# Amplifier.net
KiCad netlist of a schematic drawn in Altium Designer
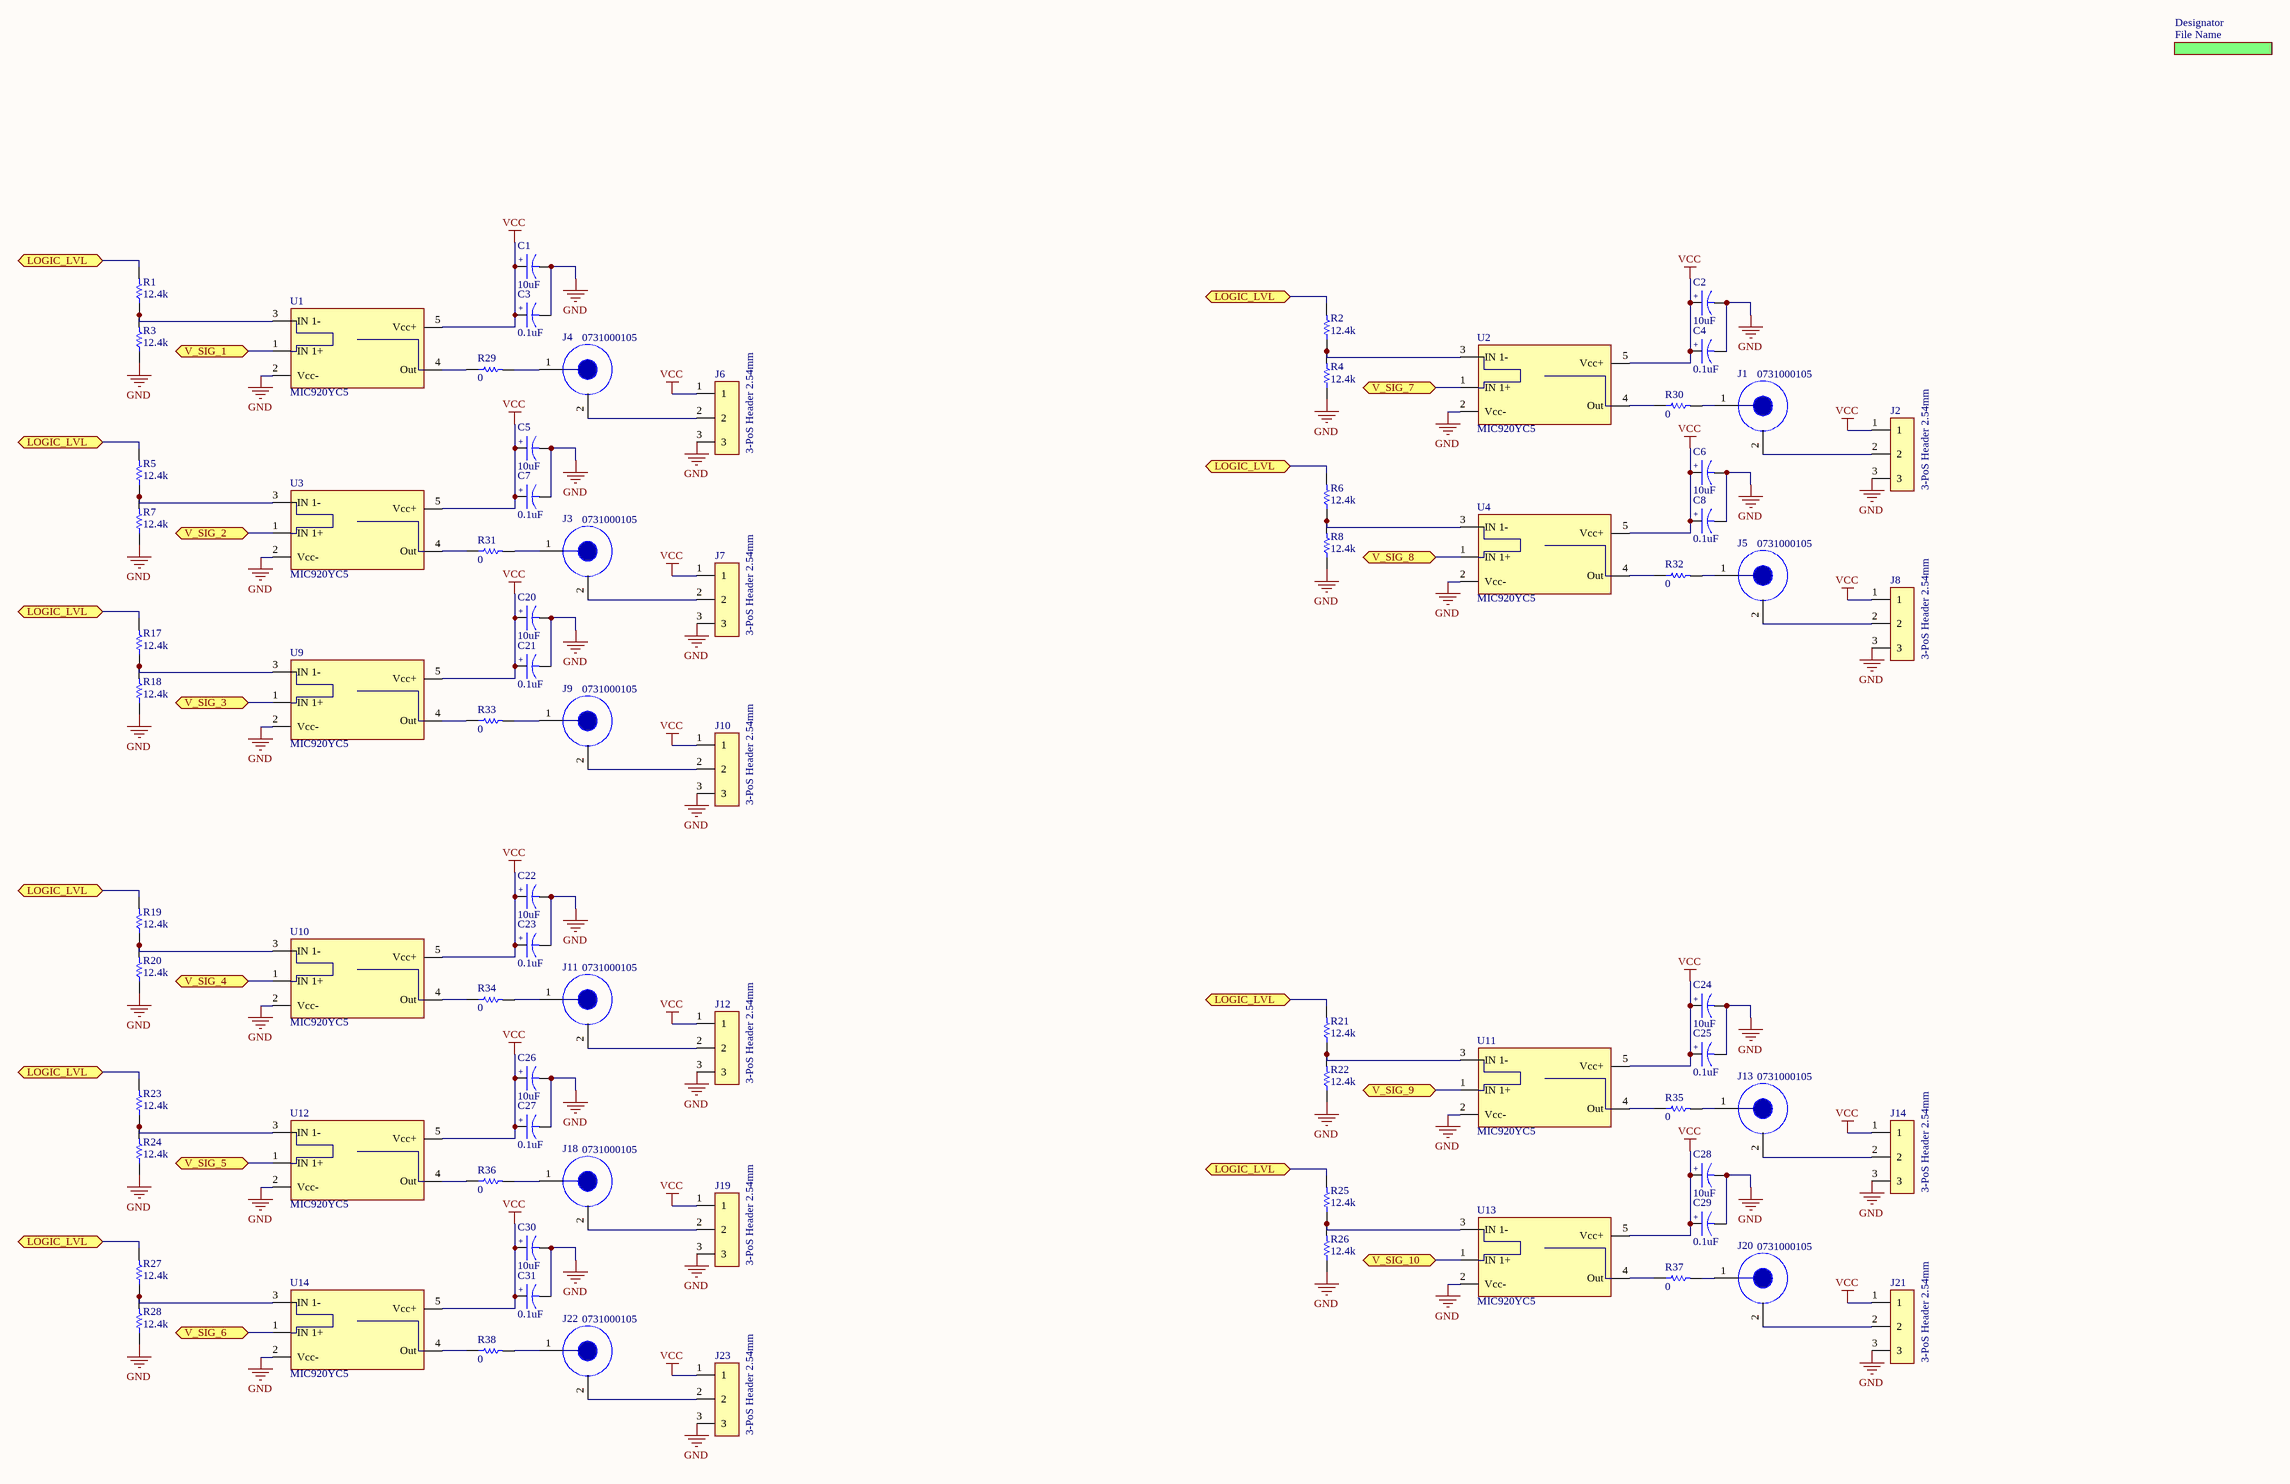
[diagram p0: Amplifier.SchDoc]

(export (version "E")
  (design (tool "Eeschema 10.0.6"))
  (components
    (comp (ref "C1")
      (value "10uF")
      (footprint "0603C")
      (description "Cap Poly")
      (libsource (lib "GENERIC_LIB") (part "CPoly"))
    )
    (comp (ref "C2")
      (value "10uF")
      (footprint "0603C")
      (description "Cap Poly")
      (libsource (lib "GENERIC_LIB") (part "CPoly"))
    )
    (comp (ref "C3")
      (value "0.1uF")
      (footprint "0603C")
      (description "Cap Poly")
      (libsource (lib "GENERIC_LIB") (part "CPoly"))
    )
    (comp (ref "C4")
      (value "0.1uF")
      (footprint "0603C")
      (description "Cap Poly")
      (libsource (lib "GENERIC_LIB") (part "CPoly"))
    )
    (comp (ref "C5")
      (value "10uF")
      (footprint "0603C")
      (description "Cap Poly")
      (libsource (lib "GENERIC_LIB") (part "CPoly"))
    )
    (comp (ref "C6")
      (value "10uF")
      (footprint "0603C")
      (description "Cap Poly")
      (libsource (lib "GENERIC_LIB") (part "CPoly"))
    )
    (comp (ref "C7")
      (value "0.1uF")
      (footprint "0603C")
      (description "Cap Poly")
      (libsource (lib "GENERIC_LIB") (part "CPoly"))
    )
    (comp (ref "C8")
      (value "0.1uF")
      (footprint "0603C")
      (description "Cap Poly")
      (libsource (lib "GENERIC_LIB") (part "CPoly"))
    )
    (comp (ref "C20")
      (value "10uF")
      (footprint "0603C")
      (description "Cap Poly")
      (libsource (lib "GENERIC_LIB") (part "CPoly"))
    )
    (comp (ref "C21")
      (value "0.1uF")
      (footprint "0603C")
      (description "Cap Poly")
      (libsource (lib "GENERIC_LIB") (part "CPoly"))
    )
    (comp (ref "C22")
      (value "10uF")
      (footprint "0603C")
      (description "Cap Poly")
      (libsource (lib "GENERIC_LIB") (part "CPoly"))
    )
    (comp (ref "C23")
      (value "0.1uF")
      (footprint "0603C")
      (description "Cap Poly")
      (libsource (lib "GENERIC_LIB") (part "CPoly"))
    )
    (comp (ref "C24")
      (value "10uF")
      (footprint "0603C")
      (description "Cap Poly")
      (libsource (lib "GENERIC_LIB") (part "CPoly"))
    )
    (comp (ref "C25")
      (value "0.1uF")
      (footprint "0603C")
      (description "Cap Poly")
      (libsource (lib "GENERIC_LIB") (part "CPoly"))
    )
    (comp (ref "C26")
      (value "10uF")
      (footprint "0603C")
      (description "Cap Poly")
      (libsource (lib "GENERIC_LIB") (part "CPoly"))
    )
    (comp (ref "C27")
      (value "0.1uF")
      (footprint "0603C")
      (description "Cap Poly")
      (libsource (lib "GENERIC_LIB") (part "CPoly"))
    )
    (comp (ref "C28")
      (value "10uF")
      (footprint "0603C")
      (description "Cap Poly")
      (libsource (lib "GENERIC_LIB") (part "CPoly"))
    )
    (comp (ref "C29")
      (value "0.1uF")
      (footprint "0603C")
      (description "Cap Poly")
      (libsource (lib "GENERIC_LIB") (part "CPoly"))
    )
    (comp (ref "C30")
      (value "10uF")
      (footprint "0603C")
      (description "Cap Poly")
      (libsource (lib "GENERIC_LIB") (part "CPoly"))
    )
    (comp (ref "C31")
      (value "0.1uF")
      (footprint "0603C")
      (description "Cap Poly")
      (libsource (lib "GENERIC_LIB") (part "CPoly"))
    )
    (comp (ref "J1")
      (value "0731000105")
      (footprint "0731000105")
      (description "BNC Connector Jack, Female Socket 50Ohm Through Hole, Right Angle Solder")
      (libsource (lib "CON_LIB") (part "0731000105"))
    )
    (comp (ref "J2")
      (value "3-PoS Header 2.54mm")
      (footprint "3-POS 2.54mm Pitch Header - duplicate")
      (libsource (lib "CON_LIB") (part "3-PoS Header"))
    )
    (comp (ref "J3")
      (value "0731000105")
      (footprint "0731000105")
      (description "BNC Connector Jack, Female Socket 50Ohm Through Hole, Right Angle Solder")
      (libsource (lib "CON_LIB") (part "0731000105"))
    )
    (comp (ref "J4")
      (value "0731000105")
      (footprint "0731000105")
      (description "BNC Connector Jack, Female Socket 50Ohm Through Hole, Right Angle Solder")
      (libsource (lib "CON_LIB") (part "0731000105"))
    )
    (comp (ref "J5")
      (value "0731000105")
      (footprint "0731000105")
      (description "BNC Connector Jack, Female Socket 50Ohm Through Hole, Right Angle Solder")
      (libsource (lib "CON_LIB") (part "0731000105"))
    )
    (comp (ref "J6")
      (value "3-PoS Header 2.54mm")
      (footprint "3-POS 2.54mm Pitch Header - duplicate")
      (libsource (lib "CON_LIB") (part "3-PoS Header"))
    )
    (comp (ref "J7")
      (value "3-PoS Header 2.54mm")
      (footprint "3-POS 2.54mm Pitch Header - duplicate")
      (libsource (lib "CON_LIB") (part "3-PoS Header"))
    )
    (comp (ref "J8")
      (value "3-PoS Header 2.54mm")
      (footprint "3-POS 2.54mm Pitch Header - duplicate")
      (libsource (lib "CON_LIB") (part "3-PoS Header"))
    )
    (comp (ref "J9")
      (value "0731000105")
      (footprint "0731000105")
      (description "BNC Connector Jack, Female Socket 50Ohm Through Hole, Right Angle Solder")
      (libsource (lib "CON_LIB") (part "0731000105"))
    )
    (comp (ref "J10")
      (value "3-PoS Header 2.54mm")
      (footprint "3-POS 2.54mm Pitch Header - duplicate")
      (libsource (lib "CON_LIB") (part "3-PoS Header"))
    )
    (comp (ref "J11")
      (value "0731000105")
      (footprint "0731000105")
      (description "BNC Connector Jack, Female Socket 50Ohm Through Hole, Right Angle Solder")
      (libsource (lib "CON_LIB") (part "0731000105"))
    )
    (comp (ref "J12")
      (value "3-PoS Header 2.54mm")
      (footprint "3-POS 2.54mm Pitch Header - duplicate")
      (libsource (lib "CON_LIB") (part "3-PoS Header"))
    )
    (comp (ref "J13")
      (value "0731000105")
      (footprint "0731000105")
      (description "BNC Connector Jack, Female Socket 50Ohm Through Hole, Right Angle Solder")
      (libsource (lib "CON_LIB") (part "0731000105"))
    )
    (comp (ref "J14")
      (value "3-PoS Header 2.54mm")
      (footprint "3-POS 2.54mm Pitch Header - duplicate")
      (libsource (lib "CON_LIB") (part "3-PoS Header"))
    )
    (comp (ref "J18")
      (value "0731000105")
      (footprint "0731000105")
      (description "BNC Connector Jack, Female Socket 50Ohm Through Hole, Right Angle Solder")
      (libsource (lib "CON_LIB") (part "0731000105"))
    )
    (comp (ref "J19")
      (value "3-PoS Header 2.54mm")
      (footprint "3-POS 2.54mm Pitch Header - duplicate")
      (libsource (lib "CON_LIB") (part "3-PoS Header"))
    )
    (comp (ref "J20")
      (value "0731000105")
      (footprint "0731000105")
      (description "BNC Connector Jack, Female Socket 50Ohm Through Hole, Right Angle Solder")
      (libsource (lib "CON_LIB") (part "0731000105"))
    )
    (comp (ref "J21")
      (value "3-PoS Header 2.54mm")
      (footprint "3-POS 2.54mm Pitch Header - duplicate")
      (libsource (lib "CON_LIB") (part "3-PoS Header"))
    )
    (comp (ref "J22")
      (value "0731000105")
      (footprint "0731000105")
      (description "BNC Connector Jack, Female Socket 50Ohm Through Hole, Right Angle Solder")
      (libsource (lib "CON_LIB") (part "0731000105"))
    )
    (comp (ref "J23")
      (value "3-PoS Header 2.54mm")
      (footprint "3-POS 2.54mm Pitch Header - duplicate")
      (libsource (lib "CON_LIB") (part "3-PoS Header"))
    )
    (comp (ref "R1")
      (value "12.4k")
      (footprint "0603C")
      (description "Resistor")
      (fields (field (name "TOLERANCE") "5%"))
      (libsource (lib "GENERIC_LIB") (part "R"))
    )
    (comp (ref "R2")
      (value "12.4k")
      (footprint "0603C")
      (description "Resistor")
      (fields (field (name "TOLERANCE") "5%"))
      (libsource (lib "GENERIC_LIB") (part "R"))
    )
    (comp (ref "R3")
      (value "12.4k")
      (footprint "0603C")
      (description "Resistor")
      (fields (field (name "TOLERANCE") "5%"))
      (libsource (lib "GENERIC_LIB") (part "R"))
    )
    (comp (ref "R4")
      (value "12.4k")
      (footprint "0603C")
      (description "Resistor")
      (fields (field (name "TOLERANCE") "5%"))
      (libsource (lib "GENERIC_LIB") (part "R"))
    )
    (comp (ref "R5")
      (value "12.4k")
      (footprint "0603C")
      (description "Resistor")
      (fields (field (name "TOLERANCE") "5%"))
      (libsource (lib "GENERIC_LIB") (part "R"))
    )
    (comp (ref "R6")
      (value "12.4k")
      (footprint "0603C")
      (description "Resistor")
      (fields (field (name "TOLERANCE") "5%"))
      (libsource (lib "GENERIC_LIB") (part "R"))
    )
    (comp (ref "R7")
      (value "12.4k")
      (footprint "0603C")
      (description "Resistor")
      (fields (field (name "TOLERANCE") "5%"))
      (libsource (lib "GENERIC_LIB") (part "R"))
    )
    (comp (ref "R8")
      (value "12.4k")
      (footprint "0603C")
      (description "Resistor")
      (fields (field (name "TOLERANCE") "5%"))
      (libsource (lib "GENERIC_LIB") (part "R"))
    )
    (comp (ref "R17")
      (value "12.4k")
      (footprint "0603C")
      (description "Resistor")
      (fields (field (name "TOLERANCE") "5%"))
      (libsource (lib "GENERIC_LIB") (part "R"))
    )
    (comp (ref "R18")
      (value "12.4k")
      (footprint "0603C")
      (description "Resistor")
      (fields (field (name "TOLERANCE") "5%"))
      (libsource (lib "GENERIC_LIB") (part "R"))
    )
    (comp (ref "R19")
      (value "12.4k")
      (footprint "0603C")
      (description "Resistor")
      (fields (field (name "TOLERANCE") "5%"))
      (libsource (lib "GENERIC_LIB") (part "R"))
    )
    (comp (ref "R20")
      (value "12.4k")
      (footprint "0603C")
      (description "Resistor")
      (fields (field (name "TOLERANCE") "5%"))
      (libsource (lib "GENERIC_LIB") (part "R"))
    )
    (comp (ref "R21")
      (value "12.4k")
      (footprint "0603C")
      (description "Resistor")
      (fields (field (name "TOLERANCE") "5%"))
      (libsource (lib "GENERIC_LIB") (part "R"))
    )
    (comp (ref "R22")
      (value "12.4k")
      (footprint "0603C")
      (description "Resistor")
      (fields (field (name "TOLERANCE") "5%"))
      (libsource (lib "GENERIC_LIB") (part "R"))
    )
    (comp (ref "R23")
      (value "12.4k")
      (footprint "0603C")
      (description "Resistor")
      (fields (field (name "TOLERANCE") "5%"))
      (libsource (lib "GENERIC_LIB") (part "R"))
    )
    (comp (ref "R24")
      (value "12.4k")
      (footprint "0603C")
      (description "Resistor")
      (fields (field (name "TOLERANCE") "5%"))
      (libsource (lib "GENERIC_LIB") (part "R"))
    )
    (comp (ref "R25")
      (value "12.4k")
      (footprint "0603C")
      (description "Resistor")
      (fields (field (name "TOLERANCE") "5%"))
      (libsource (lib "GENERIC_LIB") (part "R"))
    )
    (comp (ref "R26")
      (value "12.4k")
      (footprint "0603C")
      (description "Resistor")
      (fields (field (name "TOLERANCE") "5%"))
      (libsource (lib "GENERIC_LIB") (part "R"))
    )
    (comp (ref "R27")
      (value "12.4k")
      (footprint "0603C")
      (description "Resistor")
      (fields (field (name "TOLERANCE") "5%"))
      (libsource (lib "GENERIC_LIB") (part "R"))
    )
    (comp (ref "R28")
      (value "12.4k")
      (footprint "0603C")
      (description "Resistor")
      (fields (field (name "TOLERANCE") "5%"))
      (libsource (lib "GENERIC_LIB") (part "R"))
    )
    (comp (ref "R29")
      (value "0")
      (footprint "1206C")
      (description "Resistor")
      (fields (field (name "TOLERANCE") "5%"))
      (libsource (lib "GENERIC_LIB") (part "R"))
    )
    (comp (ref "R30")
      (value "0")
      (footprint "1206C")
      (description "Resistor")
      (fields (field (name "TOLERANCE") "5%"))
      (libsource (lib "GENERIC_LIB") (part "R"))
    )
    (comp (ref "R31")
      (value "0")
      (footprint "1206C")
      (description "Resistor")
      (fields (field (name "TOLERANCE") "5%"))
      (libsource (lib "GENERIC_LIB") (part "R"))
    )
    (comp (ref "R32")
      (value "0")
      (footprint "1206C")
      (description "Resistor")
      (fields (field (name "TOLERANCE") "5%"))
      (libsource (lib "GENERIC_LIB") (part "R"))
    )
    (comp (ref "R33")
      (value "0")
      (footprint "1206C")
      (description "Resistor")
      (fields (field (name "TOLERANCE") "5%"))
      (libsource (lib "GENERIC_LIB") (part "R"))
    )
    (comp (ref "R34")
      (value "0")
      (footprint "1206C")
      (description "Resistor")
      (fields (field (name "TOLERANCE") "5%"))
      (libsource (lib "GENERIC_LIB") (part "R"))
    )
    (comp (ref "R35")
      (value "0")
      (footprint "1206C")
      (description "Resistor")
      (fields (field (name "TOLERANCE") "5%"))
      (libsource (lib "GENERIC_LIB") (part "R"))
    )
    (comp (ref "R36")
      (value "0")
      (footprint "1206C")
      (description "Resistor")
      (fields (field (name "TOLERANCE") "5%"))
      (libsource (lib "GENERIC_LIB") (part "R"))
    )
    (comp (ref "R37")
      (value "0")
      (footprint "1206C")
      (description "Resistor")
      (fields (field (name "TOLERANCE") "5%"))
      (libsource (lib "GENERIC_LIB") (part "R"))
    )
    (comp (ref "R38")
      (value "0")
      (footprint "1206C")
      (description "Resistor")
      (fields (field (name "TOLERANCE") "5%"))
      (libsource (lib "GENERIC_LIB") (part "R"))
    )
    (comp (ref "U1")
      (value "MIC920YC5")
      (footprint "MIC920")
      (description "General Purpose Amplifier 1 Circuit SC-70-5")
      (libsource (lib "ANALOG_LIB") (part "MIC920YC5-TR"))
    )
    (comp (ref "U2")
      (value "MIC920YC5")
      (footprint "MIC920")
      (description "General Purpose Amplifier 1 Circuit SC-70-5")
      (libsource (lib "ANALOG_LIB") (part "MIC920YC5-TR"))
    )
    (comp (ref "U3")
      (value "MIC920YC5")
      (footprint "MIC920")
      (description "General Purpose Amplifier 1 Circuit SC-70-5")
      (libsource (lib "ANALOG_LIB") (part "MIC920YC5-TR"))
    )
    (comp (ref "U4")
      (value "MIC920YC5")
      (footprint "MIC920")
      (description "General Purpose Amplifier 1 Circuit SC-70-5")
      (libsource (lib "ANALOG_LIB") (part "MIC920YC5-TR"))
    )
    (comp (ref "U9")
      (value "MIC920YC5")
      (footprint "MIC920")
      (description "General Purpose Amplifier 1 Circuit SC-70-5")
      (libsource (lib "ANALOG_LIB") (part "MIC920YC5-TR"))
    )
    (comp (ref "U10")
      (value "MIC920YC5")
      (footprint "MIC920")
      (description "General Purpose Amplifier 1 Circuit SC-70-5")
      (libsource (lib "ANALOG_LIB") (part "MIC920YC5-TR"))
    )
    (comp (ref "U11")
      (value "MIC920YC5")
      (footprint "MIC920")
      (description "General Purpose Amplifier 1 Circuit SC-70-5")
      (libsource (lib "ANALOG_LIB") (part "MIC920YC5-TR"))
    )
    (comp (ref "U12")
      (value "MIC920YC5")
      (footprint "MIC920")
      (description "General Purpose Amplifier 1 Circuit SC-70-5")
      (libsource (lib "ANALOG_LIB") (part "MIC920YC5-TR"))
    )
    (comp (ref "U13")
      (value "MIC920YC5")
      (footprint "MIC920")
      (description "General Purpose Amplifier 1 Circuit SC-70-5")
      (libsource (lib "ANALOG_LIB") (part "MIC920YC5-TR"))
    )
    (comp (ref "U14")
      (value "MIC920YC5")
      (footprint "MIC920")
      (description "General Purpose Amplifier 1 Circuit SC-70-5")
      (libsource (lib "ANALOG_LIB") (part "MIC920YC5-TR"))
    )
  )
  (nets
    (net (code "1") (name "/LOGIC_LVL") (class "Default")
      (node (ref "R1") (pin "2") (pinfunction "2_2") (pintype "passive"))
      (node (ref "R17") (pin "2") (pinfunction "2_2") (pintype "passive"))
      (node (ref "R19") (pin "2") (pinfunction "2_2") (pintype "passive"))
      (node (ref "R2") (pin "2") (pinfunction "2_2") (pintype "passive"))
      (node (ref "R21") (pin "2") (pinfunction "2_2") (pintype "passive"))
      (node (ref "R23") (pin "2") (pinfunction "2_2") (pintype "passive"))
      (node (ref "R25") (pin "2") (pinfunction "2_2") (pintype "passive"))
      (node (ref "R27") (pin "2") (pinfunction "2_2") (pintype "passive"))
      (node (ref "R5") (pin "2") (pinfunction "2_2") (pintype "passive"))
      (node (ref "R6") (pin "2") (pinfunction "2_2") (pintype "passive"))
    )
    (net (code "2") (name "/V_SIG_1") (class "Default")
      (node (ref "U1") (pin "1") (pinfunction "IN_1+_1") (pintype "passive"))
    )
    (net (code "3") (name "/V_SIG_2") (class "Default")
      (node (ref "U3") (pin "1") (pinfunction "IN_1+_1") (pintype "passive"))
    )
    (net (code "4") (name "/V_SIG_3") (class "Default")
      (node (ref "U9") (pin "1") (pinfunction "IN_1+_1") (pintype "passive"))
    )
    (net (code "5") (name "/V_SIG_4") (class "Default")
      (node (ref "U10") (pin "1") (pinfunction "IN_1+_1") (pintype "passive"))
    )
    (net (code "6") (name "/V_SIG_5") (class "Default")
      (node (ref "U12") (pin "1") (pinfunction "IN_1+_1") (pintype "passive"))
    )
    (net (code "7") (name "/V_SIG_6") (class "Default")
      (node (ref "U14") (pin "1") (pinfunction "IN_1+_1") (pintype "passive"))
    )
    (net (code "8") (name "/V_SIG_7") (class "Default")
      (node (ref "U2") (pin "1") (pinfunction "IN_1+_1") (pintype "passive"))
    )
    (net (code "9") (name "/V_SIG_8") (class "Default")
      (node (ref "U4") (pin "1") (pinfunction "IN_1+_1") (pintype "passive"))
    )
    (net (code "10") (name "/V_SIG_9") (class "Default")
      (node (ref "U11") (pin "1") (pinfunction "IN_1+_1") (pintype "passive"))
    )
    (net (code "11") (name "/V_SIG_10") (class "Default")
      (node (ref "U13") (pin "1") (pinfunction "IN_1+_1") (pintype "passive"))
    )
    (net (code "12") (name "GND") (class "Default")
      (node (ref "C1") (pin "2") (pinfunction "2_2") (pintype "passive"))
      (node (ref "C2") (pin "2") (pinfunction "2_2") (pintype "passive"))
      (node (ref "C20") (pin "2") (pinfunction "2_2") (pintype "passive"))
      (node (ref "C21") (pin "2") (pinfunction "2_2") (pintype "passive"))
      (node (ref "C22") (pin "2") (pinfunction "2_2") (pintype "passive"))
      (node (ref "C23") (pin "2") (pinfunction "2_2") (pintype "passive"))
      (node (ref "C24") (pin "2") (pinfunction "2_2") (pintype "passive"))
      (node (ref "C25") (pin "2") (pinfunction "2_2") (pintype "passive"))
      (node (ref "C26") (pin "2") (pinfunction "2_2") (pintype "passive"))
      (node (ref "C27") (pin "2") (pinfunction "2_2") (pintype "passive"))
      (node (ref "C28") (pin "2") (pinfunction "2_2") (pintype "passive"))
      (node (ref "C29") (pin "2") (pinfunction "2_2") (pintype "passive"))
      (node (ref "C3") (pin "2") (pinfunction "2_2") (pintype "passive"))
      (node (ref "C30") (pin "2") (pinfunction "2_2") (pintype "passive"))
      (node (ref "C31") (pin "2") (pinfunction "2_2") (pintype "passive"))
      (node (ref "C4") (pin "2") (pinfunction "2_2") (pintype "passive"))
      (node (ref "C5") (pin "2") (pinfunction "2_2") (pintype "passive"))
      (node (ref "C6") (pin "2") (pinfunction "2_2") (pintype "passive"))
      (node (ref "C7") (pin "2") (pinfunction "2_2") (pintype "passive"))
      (node (ref "C8") (pin "2") (pinfunction "2_2") (pintype "passive"))
      (node (ref "J10") (pin "3") (pinfunction "3_3") (pintype "passive"))
      (node (ref "J12") (pin "3") (pinfunction "3_3") (pintype "passive"))
      (node (ref "J14") (pin "3") (pinfunction "3_3") (pintype "passive"))
      (node (ref "J19") (pin "3") (pinfunction "3_3") (pintype "passive"))
      (node (ref "J2") (pin "3") (pinfunction "3_3") (pintype "passive"))
      (node (ref "J21") (pin "3") (pinfunction "3_3") (pintype "passive"))
      (node (ref "J23") (pin "3") (pinfunction "3_3") (pintype "passive"))
      (node (ref "J6") (pin "3") (pinfunction "3_3") (pintype "passive"))
      (node (ref "J7") (pin "3") (pinfunction "3_3") (pintype "passive"))
      (node (ref "J8") (pin "3") (pinfunction "3_3") (pintype "passive"))
      (node (ref "R18") (pin "1") (pinfunction "1_1") (pintype "passive"))
      (node (ref "R20") (pin "1") (pinfunction "1_1") (pintype "passive"))
      (node (ref "R22") (pin "1") (pinfunction "1_1") (pintype "passive"))
      (node (ref "R24") (pin "1") (pinfunction "1_1") (pintype "passive"))
      (node (ref "R26") (pin "1") (pinfunction "1_1") (pintype "passive"))
      (node (ref "R28") (pin "1") (pinfunction "1_1") (pintype "passive"))
      (node (ref "R3") (pin "1") (pinfunction "1_1") (pintype "passive"))
      (node (ref "R4") (pin "1") (pinfunction "1_1") (pintype "passive"))
      (node (ref "R7") (pin "1") (pinfunction "1_1") (pintype "passive"))
      (node (ref "R8") (pin "1") (pinfunction "1_1") (pintype "passive"))
      (node (ref "U1") (pin "2") (pinfunction "Vcc-_2") (pintype "passive"))
      (node (ref "U10") (pin "2") (pinfunction "Vcc-_2") (pintype "passive"))
      (node (ref "U11") (pin "2") (pinfunction "Vcc-_2") (pintype "passive"))
      (node (ref "U12") (pin "2") (pinfunction "Vcc-_2") (pintype "passive"))
      (node (ref "U13") (pin "2") (pinfunction "Vcc-_2") (pintype "passive"))
      (node (ref "U14") (pin "2") (pinfunction "Vcc-_2") (pintype "passive"))
      (node (ref "U2") (pin "2") (pinfunction "Vcc-_2") (pintype "passive"))
      (node (ref "U3") (pin "2") (pinfunction "Vcc-_2") (pintype "passive"))
      (node (ref "U4") (pin "2") (pinfunction "Vcc-_2") (pintype "passive"))
      (node (ref "U9") (pin "2") (pinfunction "Vcc-_2") (pintype "passive"))
    )
    (net (code "13") (name "Net-(J1-Pad1)") (class "Default")
      (node (ref "J1") (pin "1") (pinfunction "1_1") (pintype "passive"))
      (node (ref "R30") (pin "2") (pinfunction "2_2") (pintype "passive"))
    )
    (net (code "14") (name "Net-(J1-Pad2)") (class "Default")
      (node (ref "J1") (pin "2") (pinfunction "2_2") (pintype "passive"))
      (node (ref "J2") (pin "2") (pinfunction "2_2") (pintype "passive"))
    )
    (net (code "15") (name "Net-(J3-Pad1)") (class "Default")
      (node (ref "J3") (pin "1") (pinfunction "1_1") (pintype "passive"))
      (node (ref "R31") (pin "2") (pinfunction "2_2") (pintype "passive"))
    )
    (net (code "16") (name "Net-(J3-Pad2)") (class "Default")
      (node (ref "J3") (pin "2") (pinfunction "2_2") (pintype "passive"))
      (node (ref "J7") (pin "2") (pinfunction "2_2") (pintype "passive"))
    )
    (net (code "17") (name "Net-(J4-Pad1)") (class "Default")
      (node (ref "J4") (pin "1") (pinfunction "1_1") (pintype "passive"))
      (node (ref "R29") (pin "2") (pinfunction "2_2") (pintype "passive"))
    )
    (net (code "18") (name "Net-(J4-Pad2)") (class "Default")
      (node (ref "J4") (pin "2") (pinfunction "2_2") (pintype "passive"))
      (node (ref "J6") (pin "2") (pinfunction "2_2") (pintype "passive"))
    )
    (net (code "19") (name "Net-(J5-Pad1)") (class "Default")
      (node (ref "J5") (pin "1") (pinfunction "1_1") (pintype "passive"))
      (node (ref "R32") (pin "2") (pinfunction "2_2") (pintype "passive"))
    )
    (net (code "20") (name "Net-(J5-Pad2)") (class "Default")
      (node (ref "J5") (pin "2") (pinfunction "2_2") (pintype "passive"))
      (node (ref "J8") (pin "2") (pinfunction "2_2") (pintype "passive"))
    )
    (net (code "21") (name "Net-(J9-Pad1)") (class "Default")
      (node (ref "J9") (pin "1") (pinfunction "1_1") (pintype "passive"))
      (node (ref "R33") (pin "2") (pinfunction "2_2") (pintype "passive"))
    )
    (net (code "22") (name "Net-(J10-Pad2)") (class "Default")
      (node (ref "J10") (pin "2") (pinfunction "2_2") (pintype "passive"))
      (node (ref "J9") (pin "2") (pinfunction "2_2") (pintype "passive"))
    )
    (net (code "23") (name "Net-(J11-Pad1)") (class "Default")
      (node (ref "J11") (pin "1") (pinfunction "1_1") (pintype "passive"))
      (node (ref "R34") (pin "2") (pinfunction "2_2") (pintype "passive"))
    )
    (net (code "24") (name "Net-(J11-Pad2)") (class "Default")
      (node (ref "J11") (pin "2") (pinfunction "2_2") (pintype "passive"))
      (node (ref "J12") (pin "2") (pinfunction "2_2") (pintype "passive"))
    )
    (net (code "25") (name "Net-(J13-Pad1)") (class "Default")
      (node (ref "J13") (pin "1") (pinfunction "1_1") (pintype "passive"))
      (node (ref "R35") (pin "2") (pinfunction "2_2") (pintype "passive"))
    )
    (net (code "26") (name "Net-(J13-Pad2)") (class "Default")
      (node (ref "J13") (pin "2") (pinfunction "2_2") (pintype "passive"))
      (node (ref "J14") (pin "2") (pinfunction "2_2") (pintype "passive"))
    )
    (net (code "27") (name "Net-(J18-Pad1)") (class "Default")
      (node (ref "J18") (pin "1") (pinfunction "1_1") (pintype "passive"))
      (node (ref "R36") (pin "2") (pinfunction "2_2") (pintype "passive"))
    )
    (net (code "28") (name "Net-(J18-Pad2)") (class "Default")
      (node (ref "J18") (pin "2") (pinfunction "2_2") (pintype "passive"))
      (node (ref "J19") (pin "2") (pinfunction "2_2") (pintype "passive"))
    )
    (net (code "29") (name "Net-(J20-Pad1)") (class "Default")
      (node (ref "J20") (pin "1") (pinfunction "1_1") (pintype "passive"))
      (node (ref "R37") (pin "2") (pinfunction "2_2") (pintype "passive"))
    )
    (net (code "30") (name "Net-(J20-Pad2)") (class "Default")
      (node (ref "J20") (pin "2") (pinfunction "2_2") (pintype "passive"))
      (node (ref "J21") (pin "2") (pinfunction "2_2") (pintype "passive"))
    )
    (net (code "31") (name "Net-(J22-Pad1)") (class "Default")
      (node (ref "J22") (pin "1") (pinfunction "1_1") (pintype "passive"))
      (node (ref "R38") (pin "2") (pinfunction "2_2") (pintype "passive"))
    )
    (net (code "32") (name "Net-(J22-Pad2)") (class "Default")
      (node (ref "J22") (pin "2") (pinfunction "2_2") (pintype "passive"))
      (node (ref "J23") (pin "2") (pinfunction "2_2") (pintype "passive"))
    )
    (net (code "33") (name "Net-(U1-IN_1-)") (class "Default")
      (node (ref "R1") (pin "1") (pinfunction "1_1") (pintype "passive"))
      (node (ref "R3") (pin "2") (pinfunction "2_2") (pintype "passive"))
      (node (ref "U1") (pin "3") (pinfunction "IN_1-_3") (pintype "passive"))
    )
    (net (code "34") (name "Net-(U1-Out)") (class "Default")
      (node (ref "R29") (pin "1") (pinfunction "1_1") (pintype "passive"))
      (node (ref "U1") (pin "4") (pinfunction "Out_4") (pintype "passive"))
    )
    (net (code "35") (name "Net-(U2-IN_1-)") (class "Default")
      (node (ref "R2") (pin "1") (pinfunction "1_1") (pintype "passive"))
      (node (ref "R4") (pin "2") (pinfunction "2_2") (pintype "passive"))
      (node (ref "U2") (pin "3") (pinfunction "IN_1-_3") (pintype "passive"))
    )
    (net (code "36") (name "Net-(U2-Out)") (class "Default")
      (node (ref "R30") (pin "1") (pinfunction "1_1") (pintype "passive"))
      (node (ref "U2") (pin "4") (pinfunction "Out_4") (pintype "passive"))
    )
    (net (code "37") (name "Net-(U3-IN_1-)") (class "Default")
      (node (ref "R5") (pin "1") (pinfunction "1_1") (pintype "passive"))
      (node (ref "R7") (pin "2") (pinfunction "2_2") (pintype "passive"))
      (node (ref "U3") (pin "3") (pinfunction "IN_1-_3") (pintype "passive"))
    )
    (net (code "38") (name "Net-(U3-Out)") (class "Default")
      (node (ref "R31") (pin "1") (pinfunction "1_1") (pintype "passive"))
      (node (ref "U3") (pin "4") (pinfunction "Out_4") (pintype "passive"))
    )
    (net (code "39") (name "Net-(U4-IN_1-)") (class "Default")
      (node (ref "R6") (pin "1") (pinfunction "1_1") (pintype "passive"))
      (node (ref "R8") (pin "2") (pinfunction "2_2") (pintype "passive"))
      (node (ref "U4") (pin "3") (pinfunction "IN_1-_3") (pintype "passive"))
    )
    (net (code "40") (name "Net-(U4-Out)") (class "Default")
      (node (ref "R32") (pin "1") (pinfunction "1_1") (pintype "passive"))
      (node (ref "U4") (pin "4") (pinfunction "Out_4") (pintype "passive"))
    )
    (net (code "41") (name "Net-(U9-IN_1-)") (class "Default")
      (node (ref "R17") (pin "1") (pinfunction "1_1") (pintype "passive"))
      (node (ref "R18") (pin "2") (pinfunction "2_2") (pintype "passive"))
      (node (ref "U9") (pin "3") (pinfunction "IN_1-_3") (pintype "passive"))
    )
    (net (code "42") (name "Net-(U9-Out)") (class "Default")
      (node (ref "R33") (pin "1") (pinfunction "1_1") (pintype "passive"))
      (node (ref "U9") (pin "4") (pinfunction "Out_4") (pintype "passive"))
    )
    (net (code "43") (name "Net-(U10-IN_1-)") (class "Default")
      (node (ref "R19") (pin "1") (pinfunction "1_1") (pintype "passive"))
      (node (ref "R20") (pin "2") (pinfunction "2_2") (pintype "passive"))
      (node (ref "U10") (pin "3") (pinfunction "IN_1-_3") (pintype "passive"))
    )
    (net (code "44") (name "Net-(U10-Out)") (class "Default")
      (node (ref "R34") (pin "1") (pinfunction "1_1") (pintype "passive"))
      (node (ref "U10") (pin "4") (pinfunction "Out_4") (pintype "passive"))
    )
    (net (code "45") (name "Net-(U11-IN_1-)") (class "Default")
      (node (ref "R21") (pin "1") (pinfunction "1_1") (pintype "passive"))
      (node (ref "R22") (pin "2") (pinfunction "2_2") (pintype "passive"))
      (node (ref "U11") (pin "3") (pinfunction "IN_1-_3") (pintype "passive"))
    )
    (net (code "46") (name "Net-(U11-Out)") (class "Default")
      (node (ref "R35") (pin "1") (pinfunction "1_1") (pintype "passive"))
      (node (ref "U11") (pin "4") (pinfunction "Out_4") (pintype "passive"))
    )
    (net (code "47") (name "Net-(U12-IN_1-)") (class "Default")
      (node (ref "R23") (pin "1") (pinfunction "1_1") (pintype "passive"))
      (node (ref "R24") (pin "2") (pinfunction "2_2") (pintype "passive"))
      (node (ref "U12") (pin "3") (pinfunction "IN_1-_3") (pintype "passive"))
    )
    (net (code "48") (name "Net-(U12-Out)") (class "Default")
      (node (ref "R36") (pin "1") (pinfunction "1_1") (pintype "passive"))
      (node (ref "U12") (pin "4") (pinfunction "Out_4") (pintype "passive"))
    )
    (net (code "49") (name "Net-(U13-IN_1-)") (class "Default")
      (node (ref "R25") (pin "1") (pinfunction "1_1") (pintype "passive"))
      (node (ref "R26") (pin "2") (pinfunction "2_2") (pintype "passive"))
      (node (ref "U13") (pin "3") (pinfunction "IN_1-_3") (pintype "passive"))
    )
    (net (code "50") (name "Net-(U13-Out)") (class "Default")
      (node (ref "R37") (pin "1") (pinfunction "1_1") (pintype "passive"))
      (node (ref "U13") (pin "4") (pinfunction "Out_4") (pintype "passive"))
    )
    (net (code "51") (name "Net-(U14-IN_1-)") (class "Default")
      (node (ref "R27") (pin "1") (pinfunction "1_1") (pintype "passive"))
      (node (ref "R28") (pin "2") (pinfunction "2_2") (pintype "passive"))
      (node (ref "U14") (pin "3") (pinfunction "IN_1-_3") (pintype "passive"))
    )
    (net (code "52") (name "Net-(U14-Out)") (class "Default")
      (node (ref "R38") (pin "1") (pinfunction "1_1") (pintype "passive"))
      (node (ref "U14") (pin "4") (pinfunction "Out_4") (pintype "passive"))
    )
    (net (code "53") (name "VCC") (class "Default")
      (node (ref "C1") (pin "1") (pinfunction "1_1") (pintype "passive"))
      (node (ref "C2") (pin "1") (pinfunction "1_1") (pintype "passive"))
      (node (ref "C20") (pin "1") (pinfunction "1_1") (pintype "passive"))
      (node (ref "C21") (pin "1") (pinfunction "1_1") (pintype "passive"))
      (node (ref "C22") (pin "1") (pinfunction "1_1") (pintype "passive"))
      (node (ref "C23") (pin "1") (pinfunction "1_1") (pintype "passive"))
      (node (ref "C24") (pin "1") (pinfunction "1_1") (pintype "passive"))
      (node (ref "C25") (pin "1") (pinfunction "1_1") (pintype "passive"))
      (node (ref "C26") (pin "1") (pinfunction "1_1") (pintype "passive"))
      (node (ref "C27") (pin "1") (pinfunction "1_1") (pintype "passive"))
      (node (ref "C28") (pin "1") (pinfunction "1_1") (pintype "passive"))
      (node (ref "C29") (pin "1") (pinfunction "1_1") (pintype "passive"))
      (node (ref "C3") (pin "1") (pinfunction "1_1") (pintype "passive"))
      (node (ref "C30") (pin "1") (pinfunction "1_1") (pintype "passive"))
      (node (ref "C31") (pin "1") (pinfunction "1_1") (pintype "passive"))
      (node (ref "C4") (pin "1") (pinfunction "1_1") (pintype "passive"))
      (node (ref "C5") (pin "1") (pinfunction "1_1") (pintype "passive"))
      (node (ref "C6") (pin "1") (pinfunction "1_1") (pintype "passive"))
      (node (ref "C7") (pin "1") (pinfunction "1_1") (pintype "passive"))
      (node (ref "C8") (pin "1") (pinfunction "1_1") (pintype "passive"))
      (node (ref "J10") (pin "1") (pinfunction "1_1") (pintype "passive"))
      (node (ref "J12") (pin "1") (pinfunction "1_1") (pintype "passive"))
      (node (ref "J14") (pin "1") (pinfunction "1_1") (pintype "passive"))
      (node (ref "J19") (pin "1") (pinfunction "1_1") (pintype "passive"))
      (node (ref "J2") (pin "1") (pinfunction "1_1") (pintype "passive"))
      (node (ref "J21") (pin "1") (pinfunction "1_1") (pintype "passive"))
      (node (ref "J23") (pin "1") (pinfunction "1_1") (pintype "passive"))
      (node (ref "J6") (pin "1") (pinfunction "1_1") (pintype "passive"))
      (node (ref "J7") (pin "1") (pinfunction "1_1") (pintype "passive"))
      (node (ref "J8") (pin "1") (pinfunction "1_1") (pintype "passive"))
      (node (ref "U1") (pin "5") (pinfunction "Vcc+_5") (pintype "passive"))
      (node (ref "U10") (pin "5") (pinfunction "Vcc+_5") (pintype "passive"))
      (node (ref "U11") (pin "5") (pinfunction "Vcc+_5") (pintype "passive"))
      (node (ref "U12") (pin "5") (pinfunction "Vcc+_5") (pintype "passive"))
      (node (ref "U13") (pin "5") (pinfunction "Vcc+_5") (pintype "passive"))
      (node (ref "U14") (pin "5") (pinfunction "Vcc+_5") (pintype "passive"))
      (node (ref "U2") (pin "5") (pinfunction "Vcc+_5") (pintype "passive"))
      (node (ref "U3") (pin "5") (pinfunction "Vcc+_5") (pintype "passive"))
      (node (ref "U4") (pin "5") (pinfunction "Vcc+_5") (pintype "passive"))
      (node (ref "U9") (pin "5") (pinfunction "Vcc+_5") (pintype "passive"))
    )
  )
)
